# CPU_v2_0.net
KiCad netlist of a schematic drawn in EAGLE
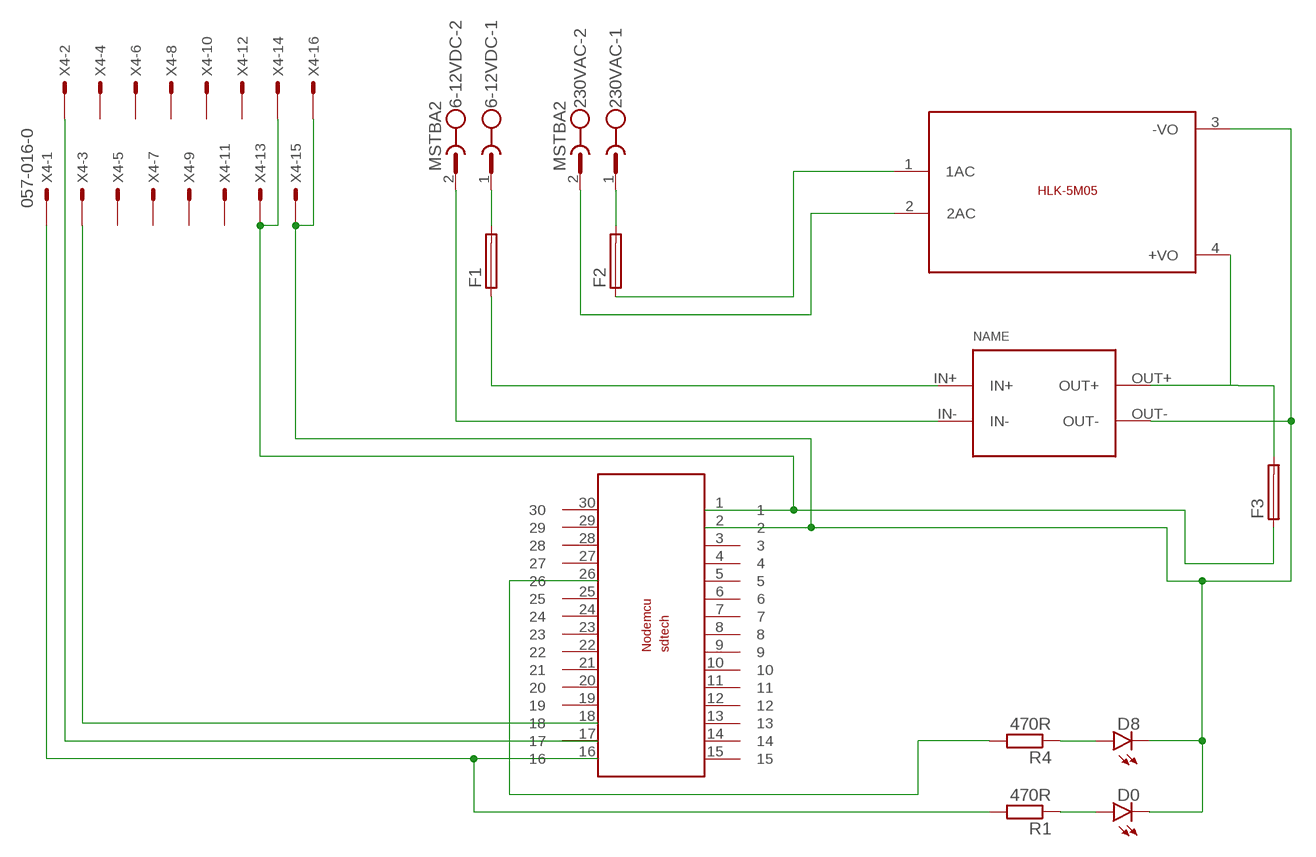
[diagram p0: schematic, sheet 1]

(export (version "E")
  (design (tool "Eeschema 10.0.6"))
  (components
    (comp (ref "6-12VDC")
      (value "MSTBA2")
      (footprint "eagle-import:MSTBA2")
      (fields (field (name "MF") "FARNELL") (field (name "MPN") "1757242"))
      (libsource (lib "eagle-import") (part "MSTBA2"))
    )
    (comp (ref "230VAC")
      (value "MSTBA2")
      (footprint "eagle-import:MSTBA2")
      (fields (field (name "MF") "FARNELL") (field (name "MPN") "1757242"))
      (libsource (lib "eagle-import") (part "MSTBA2"))
    )
    (comp (ref "D0")
      (value "LED3MM")
      (footprint "eagle-import:LED3MM")
      (libsource (lib "eagle-import") (part "LED3MM"))
    )
    (comp (ref "D8")
      (value "LED3MM")
      (footprint "eagle-import:LED3MM")
      (libsource (lib "eagle-import") (part "LED3MM"))
    )
    (comp (ref "F1")
      (value "SH22,5A")
      (footprint "eagle-import:SH22,5A")
      (fields (field (name "MPN") "0031.7701.11"))
      (libsource (lib "eagle-import") (part "SH22,5A"))
    )
    (comp (ref "F2")
      (value "SH22,5A")
      (footprint "eagle-import:SH22,5A")
      (fields (field (name "MPN") "0031.7701.11"))
      (libsource (lib "eagle-import") (part "SH22,5A"))
    )
    (comp (ref "F3")
      (value "SH22,5A")
      (footprint "eagle-import:SH22,5A")
      (fields (field (name "MPN") "0031.7701.11"))
      (libsource (lib "eagle-import") (part "SH22,5A"))
    )
    (comp (ref "R1")
      (value "470R")
      (footprint "eagle-import:0309_10")
      (libsource (lib "eagle-import") (part "R-EU_0309/10"))
    )
    (comp (ref "R4")
      (value "470R")
      (footprint "eagle-import:0309_10")
      (libsource (lib "eagle-import") (part "R-EU_0309/10"))
    )
    (comp (ref "U$1")
      (value "NODEMCUESP8266")
      (footprint "eagle-import:NODEMCUESP8266")
      (fields (field (name "SPICEPREFIX") "X"))
      (libsource (lib "eagle-import") (part "NODEMCUESP8266"))
    )
    (comp (ref "U$2")
      (value "CP8-ADJ")
      (footprint "eagle-import:CP8-ADJ")
      (libsource (lib "eagle-import") (part "CP8-ADJ"))
    )
    (comp (ref "U$3")
      (value "5VDC/5W")
      (footprint "eagle-import:HLK-5M05")
      (libsource (lib "eagle-import") (part "HLK-5M05"))
    )
    (comp (ref "X4")
      (value "057-016-0")
      (footprint "eagle-import:057-016-0")
      (libsource (lib "eagle-import") (part "057-016-0"))
    )
  )
  (nets
    (net (code "1") (name "Net-(6-12VDC-Pad1)") (class "Default")
      (node (ref "6-12VDC") (pin "1") (pinfunction "1_1") (pintype "passive"))
      (node (ref "F1") (pin "2") (pinfunction "2_2") (pintype "passive"))
    )
    (net (code "2") (name "Net-(6-12VDCB-1)") (class "Default")
      (node (ref "6-12VDC") (pin "2") (pinfunction "1_2") (pintype "passive"))
      (node (ref "U$2") (pin "IN-") (pinfunction "IN-_IN-") (pintype "passive"))
    )
    (net (code "3") (name "Net-(230VAC-Pad1)") (class "Default")
      (node (ref "230VAC") (pin "1") (pinfunction "1_1") (pintype "passive"))
      (node (ref "F2") (pin "2") (pinfunction "2_2") (pintype "passive"))
    )
    (net (code "4") (name "Net-(230VACB-1)") (class "Default")
      (node (ref "230VAC") (pin "2") (pinfunction "1_2") (pintype "passive"))
      (node (ref "U$3") (pin "2") (pinfunction "2AC_2") (pintype "bidirectional"))
    )
    (net (code "5") (name "Net-(D0-C)") (class "Default")
      (node (ref "D0") (pin "K") (pinfunction "C_K") (pintype "passive"))
      (node (ref "D8") (pin "K") (pinfunction "C_K") (pintype "passive"))
      (node (ref "U$1") (pin "2") (pinfunction "2_2") (pintype "bidirectional"))
      (node (ref "U$2") (pin "OUT-") (pinfunction "OUT-_OUT-") (pintype "passive"))
      (node (ref "U$3") (pin "3") (pinfunction "-VO_3") (pintype "bidirectional"))
      (node (ref "X4") (pin "15") (pinfunction "S_15") (pintype "passive"))
      (node (ref "X4") (pin "16") (pinfunction "S_16") (pintype "passive"))
    )
    (net (code "6") (name "Net-(D0-PadA)") (class "Default")
      (node (ref "D0") (pin "A") (pinfunction "A_A") (pintype "passive"))
      (node (ref "R1") (pin "1") (pinfunction "1_1") (pintype "passive"))
    )
    (net (code "7") (name "Net-(D8-PadA)") (class "Default")
      (node (ref "D8") (pin "A") (pinfunction "A_A") (pintype "passive"))
      (node (ref "R4") (pin "1") (pinfunction "1_1") (pintype "passive"))
    )
    (net (code "8") (name "Net-(F1-Pad1)") (class "Default")
      (node (ref "F1") (pin "1") (pinfunction "1_1") (pintype "passive"))
      (node (ref "U$2") (pin "IN+") (pinfunction "IN+_IN+") (pintype "passive"))
    )
    (net (code "9") (name "Net-(R4-Pad2)") (class "Default")
      (node (ref "R4") (pin "2") (pinfunction "2_2") (pintype "passive"))
      (node (ref "U$1") (pin "26") (pinfunction "26_26") (pintype "bidirectional"))
    )
    (net (code "10") (name "Net-(U$3-+VO)") (class "Default")
      (node (ref "F3") (pin "2") (pinfunction "2_2") (pintype "passive"))
      (node (ref "U$2") (pin "OUT+") (pinfunction "OUT+_OUT+") (pintype "passive"))
      (node (ref "U$3") (pin "4") (pinfunction "+VO_4") (pintype "bidirectional"))
    )
    (net (code "11") (name "Net-(U$3-1AC)") (class "Default")
      (node (ref "F2") (pin "1") (pinfunction "1_1") (pintype "passive"))
      (node (ref "U$3") (pin "1") (pinfunction "1AC_1") (pintype "bidirectional"))
    )
    (net (code "12") (name "Net-(X4A-S)") (class "Default")
      (node (ref "R1") (pin "2") (pinfunction "2_2") (pintype "passive"))
      (node (ref "U$1") (pin "16") (pinfunction "16_16") (pintype "bidirectional"))
      (node (ref "X4") (pin "1") (pinfunction "S_1") (pintype "passive"))
    )
    (net (code "13") (name "Net-(X4E-S)") (class "Default")
      (node (ref "F3") (pin "1") (pinfunction "1_1") (pintype "passive"))
      (node (ref "U$1") (pin "1") (pinfunction "1_1") (pintype "bidirectional"))
      (node (ref "X4") (pin "13") (pinfunction "S_13") (pintype "passive"))
      (node (ref "X4") (pin "14") (pinfunction "S_14") (pintype "passive"))
    )
    (net (code "14") (name "Net-(X4I-S)") (class "Default")
      (node (ref "U$1") (pin "17") (pinfunction "17_17") (pintype "bidirectional"))
      (node (ref "X4") (pin "2") (pinfunction "S_2") (pintype "passive"))
    )
    (net (code "15") (name "Net-(X4J-S)") (class "Default")
      (node (ref "U$1") (pin "18") (pinfunction "18_18") (pintype "bidirectional"))
      (node (ref "X4") (pin "3") (pinfunction "S_3") (pintype "passive"))
    )
    (net (code "16") (name "unconnected-(U$1-Pad3)") (class "Default")
      (node (ref "U$1") (pin "3") (pinfunction "3_3") (pintype "bidirectional"))
    )
    (net (code "17") (name "unconnected-(U$1-Pad4)") (class "Default")
      (node (ref "U$1") (pin "4") (pinfunction "4_4") (pintype "bidirectional"))
    )
    (net (code "18") (name "unconnected-(U$1-Pad5)") (class "Default")
      (node (ref "U$1") (pin "5") (pinfunction "5_5") (pintype "bidirectional"))
    )
    (net (code "19") (name "unconnected-(U$1-Pad6)") (class "Default")
      (node (ref "U$1") (pin "6") (pinfunction "6_6") (pintype "bidirectional"))
    )
    (net (code "20") (name "unconnected-(U$1-Pad7)") (class "Default")
      (node (ref "U$1") (pin "7") (pinfunction "7_7") (pintype "bidirectional"))
    )
    (net (code "21") (name "unconnected-(U$1-Pad8)") (class "Default")
      (node (ref "U$1") (pin "8") (pinfunction "8_8") (pintype "bidirectional"))
    )
    (net (code "22") (name "unconnected-(U$1-Pad9)") (class "Default")
      (node (ref "U$1") (pin "9") (pinfunction "9_9") (pintype "bidirectional"))
    )
    (net (code "23") (name "unconnected-(U$1-Pad10)") (class "Default")
      (node (ref "U$1") (pin "10") (pinfunction "10_10") (pintype "bidirectional"))
    )
    (net (code "24") (name "unconnected-(U$1-Pad11)") (class "Default")
      (node (ref "U$1") (pin "11") (pinfunction "11_11") (pintype "bidirectional"))
    )
    (net (code "25") (name "unconnected-(U$1-Pad12)") (class "Default")
      (node (ref "U$1") (pin "12") (pinfunction "12_12") (pintype "bidirectional"))
    )
    (net (code "26") (name "unconnected-(U$1-Pad13)") (class "Default")
      (node (ref "U$1") (pin "13") (pinfunction "13_13") (pintype "bidirectional"))
    )
    (net (code "27") (name "unconnected-(U$1-Pad14)") (class "Default")
      (node (ref "U$1") (pin "14") (pinfunction "14_14") (pintype "bidirectional"))
    )
    (net (code "28") (name "unconnected-(U$1-Pad15)") (class "Default")
      (node (ref "U$1") (pin "15") (pinfunction "15_15") (pintype "bidirectional"))
    )
    (net (code "29") (name "unconnected-(U$1-Pad19)") (class "Default")
      (node (ref "U$1") (pin "19") (pinfunction "19_19") (pintype "bidirectional"))
    )
    (net (code "30") (name "unconnected-(U$1-Pad20)") (class "Default")
      (node (ref "U$1") (pin "20") (pinfunction "20_20") (pintype "bidirectional"))
    )
    (net (code "31") (name "unconnected-(U$1-Pad21)") (class "Default")
      (node (ref "U$1") (pin "21") (pinfunction "21_21") (pintype "bidirectional"))
    )
    (net (code "32") (name "unconnected-(U$1-Pad22)") (class "Default")
      (node (ref "U$1") (pin "22") (pinfunction "22_22") (pintype "bidirectional"))
    )
    (net (code "33") (name "unconnected-(U$1-Pad23)") (class "Default")
      (node (ref "U$1") (pin "23") (pinfunction "23_23") (pintype "bidirectional"))
    )
    (net (code "34") (name "unconnected-(U$1-Pad24)") (class "Default")
      (node (ref "U$1") (pin "24") (pinfunction "24_24") (pintype "bidirectional"))
    )
    (net (code "35") (name "unconnected-(U$1-Pad25)") (class "Default")
      (node (ref "U$1") (pin "25") (pinfunction "25_25") (pintype "bidirectional"))
    )
    (net (code "36") (name "unconnected-(U$1-Pad27)") (class "Default")
      (node (ref "U$1") (pin "27") (pinfunction "27_27") (pintype "bidirectional"))
    )
    (net (code "37") (name "unconnected-(U$1-Pad28)") (class "Default")
      (node (ref "U$1") (pin "28") (pinfunction "28_28") (pintype "bidirectional"))
    )
    (net (code "38") (name "unconnected-(U$1-Pad29)") (class "Default")
      (node (ref "U$1") (pin "29") (pinfunction "29_29") (pintype "bidirectional"))
    )
    (net (code "39") (name "unconnected-(U$1-Pad30)") (class "Default")
      (node (ref "U$1") (pin "30") (pinfunction "30_30") (pintype "bidirectional"))
    )
    (net (code "40") (name "unconnected-(X4B-S-Pad10)") (class "Default")
      (node (ref "X4") (pin "10") (pinfunction "S_10") (pintype "passive"))
    )
    (net (code "41") (name "unconnected-(X4C-S-Pad11)") (class "Default")
      (node (ref "X4") (pin "11") (pinfunction "S_11") (pintype "passive"))
    )
    (net (code "42") (name "unconnected-(X4D-S-Pad12)") (class "Default")
      (node (ref "X4") (pin "12") (pinfunction "S_12") (pintype "passive"))
    )
    (net (code "43") (name "unconnected-(X4K-S-Pad4)") (class "Default")
      (node (ref "X4") (pin "4") (pinfunction "S_4") (pintype "passive"))
    )
    (net (code "44") (name "unconnected-(X4L-S-Pad5)") (class "Default")
      (node (ref "X4") (pin "5") (pinfunction "S_5") (pintype "passive"))
    )
    (net (code "45") (name "unconnected-(X4M-S-Pad6)") (class "Default")
      (node (ref "X4") (pin "6") (pinfunction "S_6") (pintype "passive"))
    )
    (net (code "46") (name "unconnected-(X4N-S-Pad7)") (class "Default")
      (node (ref "X4") (pin "7") (pinfunction "S_7") (pintype "passive"))
    )
    (net (code "47") (name "unconnected-(X4O-S-Pad8)") (class "Default")
      (node (ref "X4") (pin "8") (pinfunction "S_8") (pintype "passive"))
    )
    (net (code "48") (name "unconnected-(X4P-S-Pad9)") (class "Default")
      (node (ref "X4") (pin "9") (pinfunction "S_9") (pintype "passive"))
    )
  )
)
